# elv_connector.net
KiCad netlist of a schematic drawn in Altium Designer
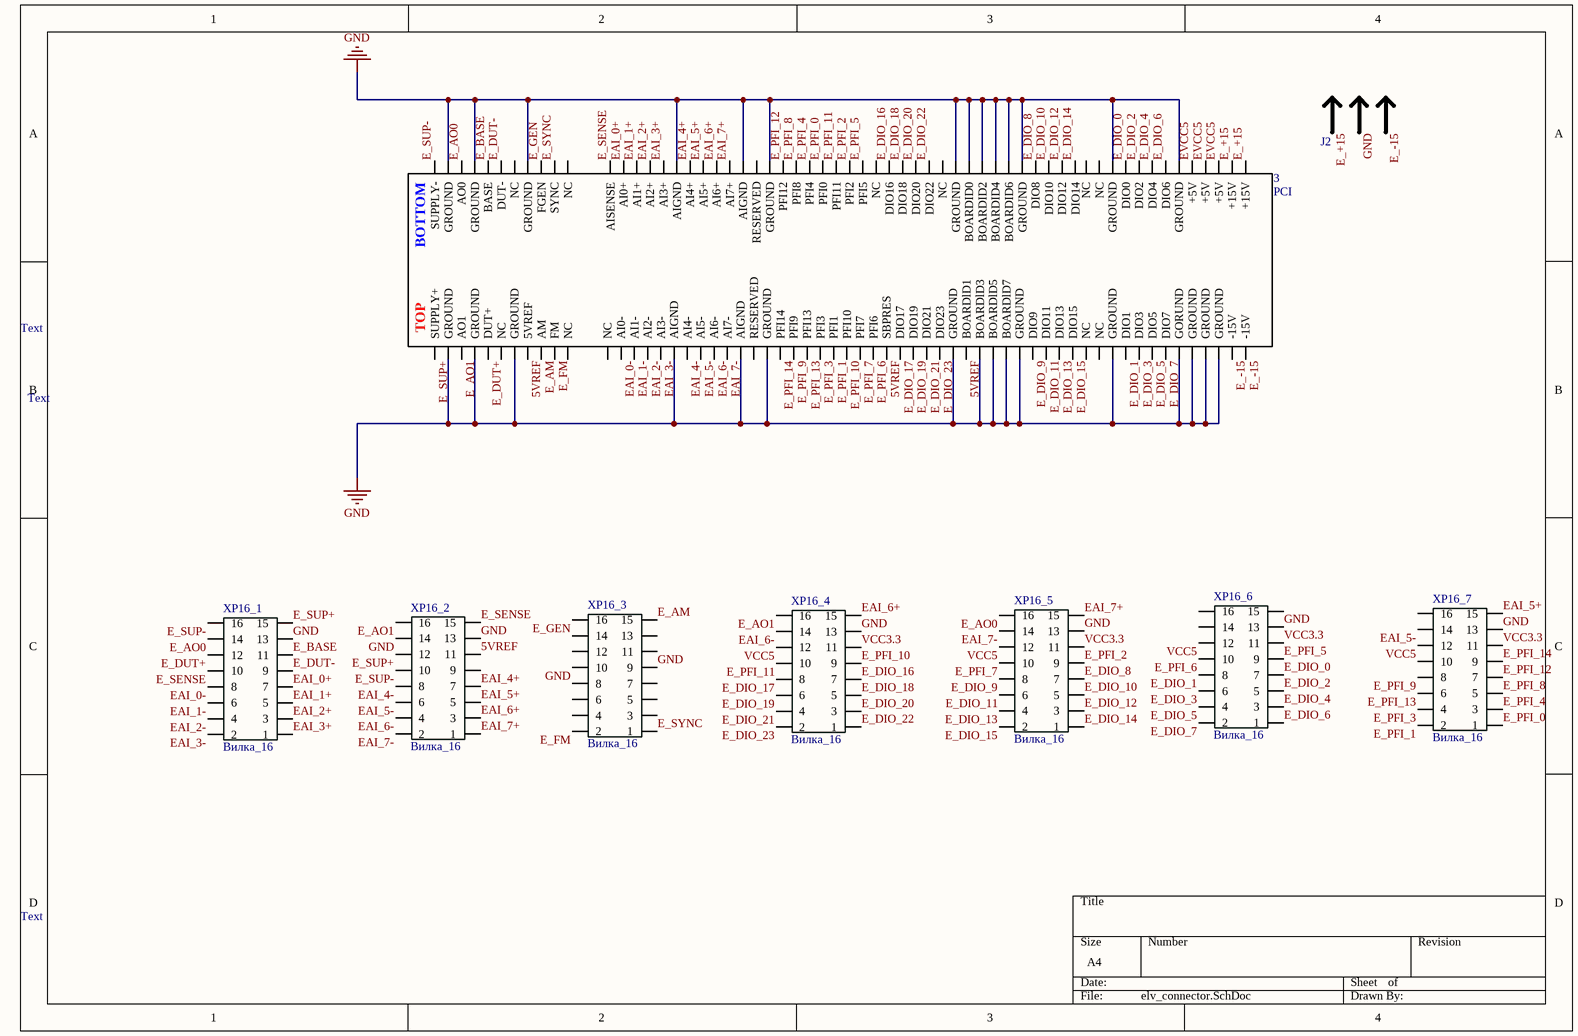
[diagram p0: elv_connector.SchDoc]

(export (version "E")
  (design (tool "Eeschema 10.0.6"))
  (components
    (comp (ref "3") (value "PCI") (footprint "elvis_lib:PCI-120") (libsource (lib "elvis_lib") (part "PCI")))
    (comp (ref "J2")
      (value "JUMPER_SWITCH_2S")
      (footprint "JUMPER_SWITCH_2S")
      (description "2 state jumper switch")
      (libsource (lib "elvis_lib") (part "JUMPER_SWITCH_2S"))
    )
    (comp (ref "XP16_1")
      (value "Вилка_16")
      (footprint "elvis_lib:DS1013-16")
      (description "16_pin")
      (libsource (lib "elvis_lib") (part "DS1013-16"))
    )
    (comp (ref "XP16_2")
      (value "Вилка_16")
      (footprint "elvis_lib:DS1013-16")
      (description "16_pin")
      (libsource (lib "elvis_lib") (part "DS1013-16"))
    )
    (comp (ref "XP16_3")
      (value "Вилка_16")
      (footprint "elvis_lib:DS1013-16")
      (description "16_pin")
      (libsource (lib "elvis_lib") (part "DS1013-16"))
    )
    (comp (ref "XP16_4")
      (value "Вилка_16")
      (footprint "elvis_lib:DS1013-16")
      (description "16_pin")
      (libsource (lib "elvis_lib") (part "DS1013-16"))
    )
    (comp (ref "XP16_5")
      (value "Вилка_16")
      (footprint "elvis_lib:DS1013-16")
      (description "16_pin")
      (libsource (lib "elvis_lib") (part "DS1013-16"))
    )
    (comp (ref "XP16_6")
      (value "Вилка_16")
      (footprint "elvis_lib:DS1013-16")
      (description "16_pin")
      (libsource (lib "elvis_lib") (part "DS1013-16"))
    )
    (comp (ref "XP16_7")
      (value "Вилка_16")
      (footprint "elvis_lib:DS1013-16")
      (description "16_pin")
      (libsource (lib "elvis_lib") (part "DS1013-16"))
    )
  )
  (nets
    (net (code "1") (name "/5VREF") (class "Default")
      (node (ref "3") (pin "32") (pinfunction "SBPRES_32") (pintype "passive"))
      (node (ref "3") (pin "38") (pinfunction "BOARDlD1_38") (pintype "passive"))
      (node (ref "3") (pin "7") (pinfunction "5VREF_7") (pintype "passive"))
      (node (ref "XP16_2") (pin "11") (pinfunction "11_11") (pintype "passive"))
    )
    (net (code "2") (name "/EAI_0+") (class "Default")
      (node (ref "3") (pin "107") (pinfunction "AI0+_107") (pintype "passive"))
      (node (ref "XP16_1") (pin "7") (pinfunction "7_7") (pintype "passive"))
    )
    (net (code "3") (name "/EAI_0-") (class "Default")
      (node (ref "3") (pin "12") (pinfunction "AI0-_12") (pintype "passive"))
      (node (ref "XP16_1") (pin "8") (pinfunction "8_8") (pintype "passive"))
    )
    (net (code "4") (name "/EAI_1+") (class "Default")
      (node (ref "3") (pin "106") (pinfunction "AI1+_106") (pintype "passive"))
      (node (ref "XP16_1") (pin "5") (pinfunction "5_5") (pintype "passive"))
    )
    (net (code "5") (name "/EAI_1-") (class "Default")
      (node (ref "3") (pin "13") (pinfunction "AI1-_13") (pintype "passive"))
      (node (ref "XP16_1") (pin "6") (pinfunction "6_6") (pintype "passive"))
    )
    (net (code "6") (name "/EAI_2+") (class "Default")
      (node (ref "3") (pin "105") (pinfunction "AI2+_105") (pintype "passive"))
      (node (ref "XP16_1") (pin "3") (pinfunction "3_3") (pintype "passive"))
    )
    (net (code "7") (name "/EAI_2-") (class "Default")
      (node (ref "3") (pin "14") (pinfunction "AI2-_14") (pintype "passive"))
      (node (ref "XP16_1") (pin "4") (pinfunction "4_4") (pintype "passive"))
    )
    (net (code "8") (name "/EAI_3+") (class "Default")
      (node (ref "3") (pin "104") (pinfunction "AI3+_104") (pintype "passive"))
      (node (ref "XP16_1") (pin "1") (pinfunction "1_1") (pintype "passive"))
    )
    (net (code "9") (name "/EAI_3-") (class "Default")
      (node (ref "3") (pin "15") (pinfunction "AI3-_15") (pintype "passive"))
      (node (ref "XP16_1") (pin "2") (pinfunction "2_2") (pintype "passive"))
    )
    (net (code "10") (name "/EAI_4+") (class "Default")
      (node (ref "3") (pin "102") (pinfunction "AI4+_102") (pintype "passive"))
      (node (ref "XP16_2") (pin "7") (pinfunction "7_7") (pintype "passive"))
    )
    (net (code "11") (name "/EAI_4-") (class "Default")
      (node (ref "3") (pin "17") (pinfunction "AI4-_17") (pintype "passive"))
      (node (ref "XP16_2") (pin "8") (pinfunction "8_8") (pintype "passive"))
    )
    (net (code "12") (name "/EAI_5+") (class "Default")
      (node (ref "3") (pin "101") (pinfunction "AI5+_101") (pintype "passive"))
      (node (ref "XP16_2") (pin "5") (pinfunction "5_5") (pintype "passive"))
      (node (ref "XP16_7") (pin "15") (pinfunction "15_15") (pintype "passive"))
    )
    (net (code "13") (name "/EAI_5-") (class "Default")
      (node (ref "3") (pin "18") (pinfunction "AI5-_18") (pintype "passive"))
      (node (ref "XP16_2") (pin "6") (pinfunction "6_6") (pintype "passive"))
      (node (ref "XP16_7") (pin "14") (pinfunction "14_14") (pintype "passive"))
    )
    (net (code "14") (name "/EAI_6+") (class "Default")
      (node (ref "3") (pin "100") (pinfunction "AI6+_100") (pintype "passive"))
      (node (ref "XP16_2") (pin "3") (pinfunction "3_3") (pintype "passive"))
      (node (ref "XP16_4") (pin "15") (pinfunction "15_15") (pintype "passive"))
    )
    (net (code "15") (name "/EAI_6-") (class "Default")
      (node (ref "3") (pin "19") (pinfunction "AI6-_19") (pintype "passive"))
      (node (ref "XP16_2") (pin "4") (pinfunction "4_4") (pintype "passive"))
      (node (ref "XP16_4") (pin "14") (pinfunction "14_14") (pintype "passive"))
    )
    (net (code "16") (name "/EAI_7+") (class "Default")
      (node (ref "3") (pin "99") (pinfunction "AI7+_99") (pintype "passive"))
      (node (ref "XP16_2") (pin "1") (pinfunction "1_1") (pintype "passive"))
      (node (ref "XP16_5") (pin "15") (pinfunction "15_15") (pintype "passive"))
    )
    (net (code "17") (name "/EAI_7-") (class "Default")
      (node (ref "3") (pin "20") (pinfunction "AI7-_20") (pintype "passive"))
      (node (ref "XP16_2") (pin "2") (pinfunction "2_2") (pintype "passive"))
      (node (ref "XP16_5") (pin "14") (pinfunction "14_14") (pintype "passive"))
    )
    (net (code "18") (name "/EVCC5") (class "Default")
      (node (ref "3") (pin "62") (pinfunction "+5V_62") (pintype "passive"))
      (node (ref "3") (pin "63") (pinfunction "+5V_63") (pintype "passive"))
      (node (ref "3") (pin "64") (pinfunction "+5V_64") (pintype "passive"))
    )
    (net (code "19") (name "/E_+15") (class "Default")
      (node (ref "3") (pin "60") (pinfunction "+15V_60") (pintype "passive"))
      (node (ref "3") (pin "61") (pinfunction "+15V_61") (pintype "passive"))
      (node (ref "J2") (pin "1") (pinfunction "1_1") (pintype "passive"))
    )
    (net (code "20") (name "/E_-15") (class "Default")
      (node (ref "3") (pin "58") (pinfunction "-15V_58") (pintype "passive"))
      (node (ref "3") (pin "59") (pinfunction "-15V_59") (pintype "passive"))
      (node (ref "J2") (pin "2") (pinfunction "2_2") (pintype "passive"))
    )
    (net (code "21") (name "/E_AM") (class "Default")
      (node (ref "3") (pin "8") (pinfunction "AM_8") (pintype "passive"))
      (node (ref "XP16_3") (pin "15") (pinfunction "15_15") (pintype "passive"))
    )
    (net (code "22") (name "/E_AO0") (class "Default")
      (node (ref "3") (pin "117") (pinfunction "AO0_117") (pintype "passive"))
      (node (ref "XP16_1") (pin "14") (pinfunction "14_14") (pintype "passive"))
      (node (ref "XP16_5") (pin "16") (pinfunction "16_16") (pintype "passive"))
    )
    (net (code "23") (name "/E_AO1") (class "Default")
      (node (ref "3") (pin "2") (pinfunction "AO1_2") (pintype "passive"))
      (node (ref "XP16_2") (pin "16") (pinfunction "16_16") (pintype "passive"))
      (node (ref "XP16_4") (pin "16") (pinfunction "16_16") (pintype "passive"))
    )
    (net (code "24") (name "/E_BASE") (class "Default")
      (node (ref "3") (pin "115") (pinfunction "BASE_115") (pintype "passive"))
      (node (ref "XP16_1") (pin "11") (pinfunction "11_11") (pintype "passive"))
    )
    (net (code "25") (name "/E_DIO_0") (class "Default")
      (node (ref "3") (pin "69") (pinfunction "DIO0_69") (pintype "passive"))
      (node (ref "XP16_6") (pin "7") (pinfunction "7_7") (pintype "passive"))
    )
    (net (code "26") (name "/E_DIO_1") (class "Default")
      (node (ref "3") (pin "50") (pinfunction "DIO1_50") (pintype "passive"))
      (node (ref "XP16_6") (pin "8") (pinfunction "8_8") (pintype "passive"))
    )
    (net (code "27") (name "/E_DIO_2") (class "Default")
      (node (ref "3") (pin "68") (pinfunction "DIO2_68") (pintype "passive"))
      (node (ref "XP16_6") (pin "5") (pinfunction "5_5") (pintype "passive"))
    )
    (net (code "28") (name "/E_DIO_3") (class "Default")
      (node (ref "3") (pin "51") (pinfunction "DIO3_51") (pintype "passive"))
      (node (ref "XP16_6") (pin "6") (pinfunction "6_6") (pintype "passive"))
    )
    (net (code "29") (name "/E_DIO_4") (class "Default")
      (node (ref "3") (pin "67") (pinfunction "DIO4_67") (pintype "passive"))
      (node (ref "XP16_6") (pin "3") (pinfunction "3_3") (pintype "passive"))
    )
    (net (code "30") (name "/E_DIO_5") (class "Default")
      (node (ref "3") (pin "52") (pinfunction "DIO5_52") (pintype "passive"))
      (node (ref "XP16_6") (pin "4") (pinfunction "4_4") (pintype "passive"))
    )
    (net (code "31") (name "/E_DIO_6") (class "Default")
      (node (ref "3") (pin "66") (pinfunction "DIO6_66") (pintype "passive"))
      (node (ref "XP16_6") (pin "1") (pinfunction "1_1") (pintype "passive"))
    )
    (net (code "32") (name "/E_DIO_7") (class "Default")
      (node (ref "3") (pin "53") (pinfunction "DIO7_53") (pintype "passive"))
      (node (ref "XP16_6") (pin "2") (pinfunction "2_2") (pintype "passive"))
    )
    (net (code "33") (name "/E_DIO_8") (class "Default")
      (node (ref "3") (pin "76") (pinfunction "DIO8_76") (pintype "passive"))
      (node (ref "XP16_5") (pin "7") (pinfunction "7_7") (pintype "passive"))
    )
    (net (code "34") (name "/E_DIO_9") (class "Default")
      (node (ref "3") (pin "43") (pinfunction "DIO9_43") (pintype "passive"))
      (node (ref "XP16_5") (pin "8") (pinfunction "8_8") (pintype "passive"))
    )
    (net (code "35") (name "/E_DIO_10") (class "Default")
      (node (ref "3") (pin "75") (pinfunction "DIO10_75") (pintype "passive"))
      (node (ref "XP16_5") (pin "5") (pinfunction "5_5") (pintype "passive"))
    )
    (net (code "36") (name "/E_DIO_11") (class "Default")
      (node (ref "3") (pin "44") (pinfunction "DIO11_44") (pintype "passive"))
      (node (ref "XP16_5") (pin "6") (pinfunction "6_6") (pintype "passive"))
    )
    (net (code "37") (name "/E_DIO_12") (class "Default")
      (node (ref "3") (pin "74") (pinfunction "DIO12_74") (pintype "passive"))
      (node (ref "XP16_5") (pin "3") (pinfunction "3_3") (pintype "passive"))
    )
    (net (code "38") (name "/E_DIO_13") (class "Default")
      (node (ref "3") (pin "45") (pinfunction "DIO13_45") (pintype "passive"))
      (node (ref "XP16_5") (pin "4") (pinfunction "4_4") (pintype "passive"))
    )
    (net (code "39") (name "/E_DIO_14") (class "Default")
      (node (ref "3") (pin "73") (pinfunction "DIO14_73") (pintype "passive"))
      (node (ref "XP16_5") (pin "1") (pinfunction "1_1") (pintype "passive"))
    )
    (net (code "40") (name "/E_DIO_15") (class "Default")
      (node (ref "3") (pin "46") (pinfunction "DIO15_46") (pintype "passive"))
      (node (ref "XP16_5") (pin "2") (pinfunction "2_2") (pintype "passive"))
    )
    (net (code "41") (name "/E_DIO_16") (class "Default")
      (node (ref "3") (pin "87") (pinfunction "DIO16_87") (pintype "passive"))
      (node (ref "XP16_4") (pin "7") (pinfunction "7_7") (pintype "passive"))
    )
    (net (code "42") (name "/E_DIO_17") (class "Default")
      (node (ref "3") (pin "33") (pinfunction "DIO17_33") (pintype "passive"))
      (node (ref "XP16_4") (pin "8") (pinfunction "8_8") (pintype "passive"))
    )
    (net (code "43") (name "/E_DIO_18") (class "Default")
      (node (ref "3") (pin "86") (pinfunction "DIO18_86") (pintype "passive"))
      (node (ref "XP16_4") (pin "5") (pinfunction "5_5") (pintype "passive"))
    )
    (net (code "44") (name "/E_DIO_19") (class "Default")
      (node (ref "3") (pin "34") (pinfunction "DIO19_34") (pintype "passive"))
      (node (ref "XP16_4") (pin "6") (pinfunction "6_6") (pintype "passive"))
    )
    (net (code "45") (name "/E_DIO_20") (class "Default")
      (node (ref "3") (pin "85") (pinfunction "DIO20_85") (pintype "passive"))
      (node (ref "XP16_4") (pin "3") (pinfunction "3_3") (pintype "passive"))
    )
    (net (code "46") (name "/E_DIO_21") (class "Default")
      (node (ref "3") (pin "35") (pinfunction "DIO21_35") (pintype "passive"))
      (node (ref "XP16_4") (pin "4") (pinfunction "4_4") (pintype "passive"))
    )
    (net (code "47") (name "/E_DIO_22") (class "Default")
      (node (ref "3") (pin "84") (pinfunction "DIO22_84") (pintype "passive"))
      (node (ref "XP16_4") (pin "1") (pinfunction "1_1") (pintype "passive"))
    )
    (net (code "48") (name "/E_DIO_23") (class "Default")
      (node (ref "3") (pin "36") (pinfunction "DIO23_36") (pintype "passive"))
      (node (ref "XP16_4") (pin "2") (pinfunction "2_2") (pintype "passive"))
    )
    (net (code "49") (name "/E_DUT+") (class "Default")
      (node (ref "3") (pin "4") (pinfunction "DUT+_4") (pintype "passive"))
      (node (ref "XP16_1") (pin "12") (pinfunction "12_12") (pintype "passive"))
    )
    (net (code "50") (name "/E_DUT-") (class "Default")
      (node (ref "3") (pin "114") (pinfunction "DUT-_114") (pintype "passive"))
      (node (ref "XP16_1") (pin "9") (pinfunction "9_9") (pintype "passive"))
    )
    (net (code "51") (name "/E_FM") (class "Default")
      (node (ref "3") (pin "9") (pinfunction "FM_9") (pintype "passive"))
      (node (ref "XP16_3") (pin "2") (pinfunction "2_2") (pintype "passive"))
    )
    (net (code "52") (name "/E_GEN") (class "Default")
      (node (ref "3") (pin "111") (pinfunction "FGEN_111") (pintype "passive"))
      (node (ref "XP16_3") (pin "16") (pinfunction "16_16") (pintype "passive"))
    )
    (net (code "53") (name "/E_PFI_0") (class "Default")
      (node (ref "3") (pin "92") (pinfunction "PFI0_92") (pintype "passive"))
      (node (ref "XP16_7") (pin "1") (pinfunction "1_1") (pintype "passive"))
    )
    (net (code "54") (name "/E_PFI_1") (class "Default")
      (node (ref "3") (pin "28") (pinfunction "PFI1_28") (pintype "passive"))
      (node (ref "XP16_7") (pin "2") (pinfunction "2_2") (pintype "passive"))
    )
    (net (code "55") (name "/E_PFI_2") (class "Default")
      (node (ref "3") (pin "90") (pinfunction "PFI2_90") (pintype "passive"))
      (node (ref "XP16_5") (pin "9") (pinfunction "9_9") (pintype "passive"))
    )
    (net (code "56") (name "/E_PFI_3") (class "Default")
      (node (ref "3") (pin "27") (pinfunction "PFI3_27") (pintype "passive"))
      (node (ref "XP16_7") (pin "4") (pinfunction "4_4") (pintype "passive"))
    )
    (net (code "57") (name "/E_PFI_4") (class "Default")
      (node (ref "3") (pin "93") (pinfunction "PFI4_93") (pintype "passive"))
      (node (ref "XP16_7") (pin "3") (pinfunction "3_3") (pintype "passive"))
    )
    (net (code "58") (name "/E_PFI_5") (class "Default")
      (node (ref "3") (pin "89") (pinfunction "PFI5_89") (pintype "passive"))
      (node (ref "XP16_6") (pin "9") (pinfunction "9_9") (pintype "passive"))
    )
    (net (code "59") (name "/E_PFI_6") (class "Default")
      (node (ref "3") (pin "31") (pinfunction "PFI6_31") (pintype "passive"))
      (node (ref "XP16_6") (pin "10") (pinfunction "10_10") (pintype "passive"))
    )
    (net (code "60") (name "/E_PFI_7") (class "Default")
      (node (ref "3") (pin "30") (pinfunction "PFI7_30") (pintype "passive"))
      (node (ref "XP16_5") (pin "10") (pinfunction "10_10") (pintype "passive"))
    )
    (net (code "61") (name "/E_PFI_8") (class "Default")
      (node (ref "3") (pin "94") (pinfunction "PFI8_94") (pintype "passive"))
      (node (ref "XP16_7") (pin "5") (pinfunction "5_5") (pintype "passive"))
    )
    (net (code "62") (name "/E_PFI_9") (class "Default")
      (node (ref "3") (pin "25") (pinfunction "PFI9_25") (pintype "passive"))
      (node (ref "XP16_7") (pin "8") (pinfunction "8_8") (pintype "passive"))
    )
    (net (code "63") (name "/E_PFI_10") (class "Default")
      (node (ref "3") (pin "29") (pinfunction "PFI10_29") (pintype "passive"))
      (node (ref "XP16_4") (pin "9") (pinfunction "9_9") (pintype "passive"))
    )
    (net (code "64") (name "/E_PFI_11") (class "Default")
      (node (ref "3") (pin "91") (pinfunction "PFI11_91") (pintype "passive"))
      (node (ref "XP16_4") (pin "10") (pinfunction "10_10") (pintype "passive"))
    )
    (net (code "65") (name "/E_PFI_12") (class "Default")
      (node (ref "3") (pin "95") (pinfunction "PFI12_95") (pintype "passive"))
      (node (ref "XP16_7") (pin "7") (pinfunction "7_7") (pintype "passive"))
    )
    (net (code "66") (name "/E_PFI_13") (class "Default")
      (node (ref "3") (pin "26") (pinfunction "PFI13_26") (pintype "passive"))
      (node (ref "XP16_7") (pin "6") (pinfunction "6_6") (pintype "passive"))
    )
    (net (code "67") (name "/E_PFI_14") (class "Default")
      (node (ref "3") (pin "24") (pinfunction "PFI14_24") (pintype "passive"))
      (node (ref "XP16_7") (pin "9") (pinfunction "9_9") (pintype "passive"))
    )
    (net (code "68") (name "/E_SENSE") (class "Default")
      (node (ref "3") (pin "108") (pinfunction "AISENSE_108") (pintype "passive"))
      (node (ref "XP16_1") (pin "10") (pinfunction "10_10") (pintype "passive"))
      (node (ref "XP16_2") (pin "15") (pinfunction "15_15") (pintype "passive"))
    )
    (net (code "69") (name "/E_SUP+") (class "Default")
      (node (ref "3") (pin "0") (pinfunction "SUPPLY+_0") (pintype "passive"))
      (node (ref "XP16_1") (pin "15") (pinfunction "15_15") (pintype "passive"))
      (node (ref "XP16_2") (pin "12") (pinfunction "12_12") (pintype "passive"))
    )
    (net (code "70") (name "/E_SUP-") (class "Default")
      (node (ref "3") (pin "119") (pinfunction "SUPPLY-_119") (pintype "passive"))
      (node (ref "XP16_1") (pin "16") (pinfunction "16_16") (pintype "passive"))
      (node (ref "XP16_2") (pin "10") (pinfunction "10_10") (pintype "passive"))
    )
    (net (code "71") (name "/E_SYNC") (class "Default")
      (node (ref "3") (pin "110") (pinfunction "SYNC_110") (pintype "passive"))
      (node (ref "XP16_3") (pin "1") (pinfunction "1_1") (pintype "passive"))
    )
    (net (code "72") (name "/VCC3.3") (class "Default")
      (node (ref "XP16_4") (pin "11") (pinfunction "11_11") (pintype "passive"))
      (node (ref "XP16_5") (pin "11") (pinfunction "11_11") (pintype "passive"))
      (node (ref "XP16_6") (pin "11") (pinfunction "11_11") (pintype "passive"))
      (node (ref "XP16_7") (pin "11") (pinfunction "11_11") (pintype "passive"))
    )
    (net (code "73") (name "/VCC5") (class "Default")
      (node (ref "XP16_4") (pin "12") (pinfunction "12_12") (pintype "passive"))
      (node (ref "XP16_5") (pin "12") (pinfunction "12_12") (pintype "passive"))
      (node (ref "XP16_6") (pin "12") (pinfunction "12_12") (pintype "passive"))
      (node (ref "XP16_7") (pin "12") (pinfunction "12_12") (pintype "passive"))
    )
    (net (code "74") (name "GND") (class "Default")
      (node (ref "3") (pin "1") (pinfunction "GROUND_1") (pintype "passive"))
      (node (ref "3") (pin "103") (pinfunction "AIGND_103") (pintype "passive"))
      (node (ref "3") (pin "112") (pinfunction "GROUND_112") (pintype "passive"))
      (node (ref "3") (pin "116") (pinfunction "GROUND_116") (pintype "passive"))
      (node (ref "3") (pin "118") (pinfunction "GROUND_118") (pintype "passive"))
      (node (ref "3") (pin "16") (pinfunction "AIGND_16") (pintype "passive"))
      (node (ref "3") (pin "21") (pinfunction "AIGND_21") (pintype "passive"))
      (node (ref "3") (pin "23") (pinfunction "GROUND_23") (pintype "passive"))
      (node (ref "3") (pin "3") (pinfunction "GROUND_3") (pintype "passive"))
      (node (ref "3") (pin "37") (pinfunction "GROUND_37") (pintype "passive"))
      (node (ref "3") (pin "39") (pinfunction "BOARDlD3_39") (pintype "passive"))
      (node (ref "3") (pin "40") (pinfunction "BOARDlD5_40") (pintype "passive"))
      (node (ref "3") (pin "41") (pinfunction "BOARDlD7_41") (pintype "passive"))
      (node (ref "3") (pin "42") (pinfunction "GROUND_42") (pintype "passive"))
      (node (ref "3") (pin "49") (pinfunction "GROUND_49") (pintype "passive"))
      (node (ref "3") (pin "54") (pinfunction "GORUND_54") (pintype "passive"))
      (node (ref "3") (pin "55") (pinfunction "GROUND_55") (pintype "passive"))
      (node (ref "3") (pin "56") (pinfunction "GROUND_56") (pintype "passive"))
      (node (ref "3") (pin "57") (pinfunction "GROUND_57") (pintype "passive"))
      (node (ref "3") (pin "6") (pinfunction "GROUND_6") (pintype "passive"))
      (node (ref "3") (pin "65") (pinfunction "GROUND_65") (pintype "passive"))
      (node (ref "3") (pin "70") (pinfunction "GROUND_70") (pintype "passive"))
      (node (ref "3") (pin "77") (pinfunction "GROUND_77") (pintype "passive"))
      (node (ref "3") (pin "78") (pinfunction "BOARDID6_78") (pintype "passive"))
      (node (ref "3") (pin "79") (pinfunction "BOARDID4_79") (pintype "passive"))
      (node (ref "3") (pin "80") (pinfunction "BOARDID2_80") (pintype "passive"))
      (node (ref "3") (pin "81") (pinfunction "BOARDID0_81") (pintype "passive"))
      (node (ref "3") (pin "82") (pinfunction "GROUND_82") (pintype "passive"))
      (node (ref "3") (pin "96") (pinfunction "GROUND_96") (pintype "passive"))
      (node (ref "3") (pin "98") (pinfunction "AIGND_98") (pintype "passive"))
      (node (ref "J2") (pin "0") (pinfunction "0_0") (pintype "passive"))
      (node (ref "XP16_1") (pin "13") (pinfunction "13_13") (pintype "passive"))
      (node (ref "XP16_2") (pin "13") (pinfunction "13_13") (pintype "passive"))
      (node (ref "XP16_2") (pin "14") (pinfunction "14_14") (pintype "passive"))
      (node (ref "XP16_3") (pin "10") (pinfunction "10_10") (pintype "passive"))
      (node (ref "XP16_3") (pin "9") (pinfunction "9_9") (pintype "passive"))
      (node (ref "XP16_4") (pin "13") (pinfunction "13_13") (pintype "passive"))
      (node (ref "XP16_5") (pin "13") (pinfunction "13_13") (pintype "passive"))
      (node (ref "XP16_6") (pin "13") (pinfunction "13_13") (pintype "passive"))
      (node (ref "XP16_7") (pin "13") (pinfunction "13_13") (pintype "passive"))
    )
    (net (code "75") (name "unconnected-(3-NC-Pad5)") (class "Default")
      (node (ref "3") (pin "5") (pinfunction "NC_5") (pintype "passive"))
    )
    (net (code "76") (name "unconnected-(3-NC-Pad10)") (class "Default")
      (node (ref "3") (pin "10") (pinfunction "NC_10") (pintype "passive"))
    )
    (net (code "77") (name "unconnected-(3-NC-Pad11)") (class "Default")
      (node (ref "3") (pin "11") (pinfunction "NC_11") (pintype "passive"))
    )
    (net (code "78") (name "unconnected-(3-NC-Pad47)") (class "Default")
      (node (ref "3") (pin "47") (pinfunction "NC_47") (pintype "passive"))
    )
    (net (code "79") (name "unconnected-(3-NC-Pad48)") (class "Default")
      (node (ref "3") (pin "48") (pinfunction "NC_48") (pintype "passive"))
    )
    (net (code "80") (name "unconnected-(3-NC-Pad71)") (class "Default")
      (node (ref "3") (pin "71") (pinfunction "NC_71") (pintype "passive"))
    )
    (net (code "81") (name "unconnected-(3-NC-Pad72)") (class "Default")
      (node (ref "3") (pin "72") (pinfunction "NC_72") (pintype "passive"))
    )
    (net (code "82") (name "unconnected-(3-NC-Pad83)") (class "Default")
      (node (ref "3") (pin "83") (pinfunction "NC_83") (pintype "passive"))
    )
    (net (code "83") (name "unconnected-(3-NC-Pad88)") (class "Default")
      (node (ref "3") (pin "88") (pinfunction "NC_88") (pintype "passive"))
    )
    (net (code "84") (name "unconnected-(3-NC-Pad109)") (class "Default")
      (node (ref "3") (pin "109") (pinfunction "NC_109") (pintype "passive"))
    )
    (net (code "85") (name "unconnected-(3-NC-Pad113)") (class "Default")
      (node (ref "3") (pin "113") (pinfunction "NC_113") (pintype "passive"))
    )
    (net (code "86") (name "unconnected-(3-RESERVED-Pad22)") (class "Default")
      (node (ref "3") (pin "22") (pinfunction "RESERVED_22") (pintype "passive"))
    )
    (net (code "87") (name "unconnected-(3-RESERVED-Pad97)") (class "Default")
      (node (ref "3") (pin "97") (pinfunction "RESERVED_97") (pintype "passive"))
    )
    (net (code "88") (name "unconnected-(XP16_2-Pad9)") (class "Default")
      (node (ref "XP16_2") (pin "9") (pinfunction "9_9") (pintype "passive"))
    )
    (net (code "89") (name "unconnected-(XP16_3-Pad3)") (class "Default")
      (node (ref "XP16_3") (pin "3") (pinfunction "3_3") (pintype "passive"))
    )
    (net (code "90") (name "unconnected-(XP16_3-Pad4)") (class "Default")
      (node (ref "XP16_3") (pin "4") (pinfunction "4_4") (pintype "passive"))
    )
    (net (code "91") (name "unconnected-(XP16_3-Pad5)") (class "Default")
      (node (ref "XP16_3") (pin "5") (pinfunction "5_5") (pintype "passive"))
    )
    (net (code "92") (name "unconnected-(XP16_3-Pad6)") (class "Default")
      (node (ref "XP16_3") (pin "6") (pinfunction "6_6") (pintype "passive"))
    )
    (net (code "93") (name "unconnected-(XP16_3-Pad7)") (class "Default")
      (node (ref "XP16_3") (pin "7") (pinfunction "7_7") (pintype "passive"))
    )
    (net (code "94") (name "unconnected-(XP16_3-Pad8)") (class "Default")
      (node (ref "XP16_3") (pin "8") (pinfunction "8_8") (pintype "passive"))
    )
    (net (code "95") (name "unconnected-(XP16_3-Pad11)") (class "Default")
      (node (ref "XP16_3") (pin "11") (pinfunction "11_11") (pintype "passive"))
    )
    (net (code "96") (name "unconnected-(XP16_3-Pad12)") (class "Default")
      (node (ref "XP16_3") (pin "12") (pinfunction "12_12") (pintype "passive"))
    )
    (net (code "97") (name "unconnected-(XP16_3-Pad13)") (class "Default")
      (node (ref "XP16_3") (pin "13") (pinfunction "13_13") (pintype "passive"))
    )
    (net (code "98") (name "unconnected-(XP16_3-Pad14)") (class "Default")
      (node (ref "XP16_3") (pin "14") (pinfunction "14_14") (pintype "passive"))
    )
    (net (code "99") (name "unconnected-(XP16_6-Pad14)") (class "Default")
      (node (ref "XP16_6") (pin "14") (pinfunction "14_14") (pintype "passive"))
    )
    (net (code "100") (name "unconnected-(XP16_6-Pad15)") (class "Default")
      (node (ref "XP16_6") (pin "15") (pinfunction "15_15") (pintype "passive"))
    )
    (net (code "101") (name "unconnected-(XP16_6-Pad16)") (class "Default")
      (node (ref "XP16_6") (pin "16") (pinfunction "16_16") (pintype "passive"))
    )
    (net (code "102") (name "unconnected-(XP16_7-Pad10)") (class "Default")
      (node (ref "XP16_7") (pin "10") (pinfunction "10_10") (pintype "passive"))
    )
    (net (code "103") (name "unconnected-(XP16_7-Pad16)") (class "Default")
      (node (ref "XP16_7") (pin "16") (pinfunction "16_16") (pintype "passive"))
    )
  )
)
